# PowerSCH.net
KiCad netlist of a schematic drawn in Altium Designer
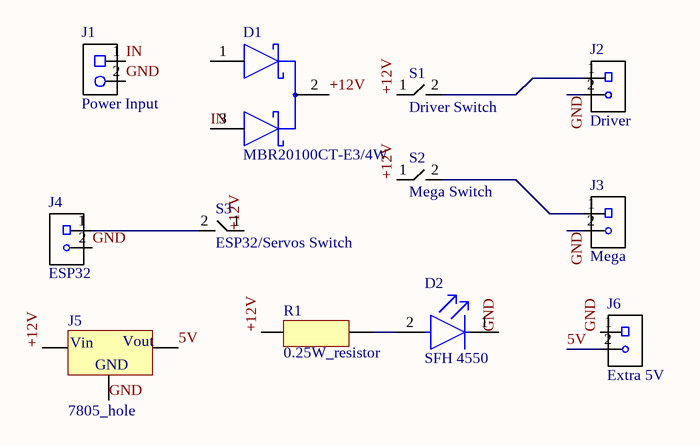
[diagram p0: PowerSCH.SchDoc]

(export (version "E")
  (design (tool "Eeschema 10.0.6"))
  (components
    (comp (ref "D1")
      (value "MBR20100CT-E3/4W")
      (footprint "FP-MBR20100CT-E3-4W-MFG")
      (description "MBR20100CT-E3/4W Dual Common-Cathode High-Voltage Schottky Rectifier")
      (libsource (lib "Altium Content Vault") (part "213139fa27cf652ab25f6c90a0a0ee5"))
    )
    (comp (ref "D2")
      (value "SFH 4550")
      (footprint "FP-SFH_4550-MFG")
      (description "Infrared Emitter, 3 , T-1 3/4 (5mm), 100 mA, 1.5 V, 12 ns, 12 ns")
      (fields (field (name "OCTOPART") "https://octopart.com/sfh+4550-osram+opto-55410894"))
      (libsource (lib "Altium Content Vault") (part "75a0115997dd6a71327e26aab64f6f8"))
    )
    (comp (ref "J1")
      (value "Power Input")
      (footprint "Barrier Terminal 2P")
      (fields
        (field (name "MANUFACTURER") "DORABO")
        (field (name "MANUFACTURER PART #") "DBT50G-9.5-2P-BK-P OGC")
        (field (name "SELLER PART #") "3496300101634")
      )
      (libsource (lib "SCH_LIB2SchLib") (part "Barrier Terminal 2P"))
    )
    (comp (ref "J2")
      (value "Driver")
      (footprint "Screw Terminal 2 pins")
      (fields (field (name "MANUFACTURER") "CUI") (field (name "MANUFACTURER PART NUMBER") "TB004-508-02BE"))
      (libsource (lib "SCH_LIB2SchLib") (part "Screw Terminal 2 pins"))
    )
    (comp (ref "J3")
      (value "Mega")
      (footprint "Screw Terminal 2 pins")
      (fields (field (name "MANUFACTURER") "CUI") (field (name "MANUFACTURER PART NUMBER") "TB004-508-02BE"))
      (libsource (lib "SCH_LIB2SchLib") (part "Screw Terminal 2 pins"))
    )
    (comp (ref "J4")
      (value "ESP32")
      (footprint "Screw Terminal 2 pins")
      (fields (field (name "MANUFACTURER") "CUI") (field (name "MANUFACTURER PART NUMBER") "TB004-508-02BE"))
      (libsource (lib "SCH_LIB2SchLib") (part "Screw Terminal 2 pins"))
    )
    (comp (ref "J5")
      (value "7805_hole")
      (footprint "780X_hole")
      (libsource (lib "Negm_3") (part "7805_hole"))
    )
    (comp (ref "J6")
      (value "Extra 5V")
      (footprint "Screw Terminal 2 pins")
      (fields (field (name "MANUFACTURER") "CUI") (field (name "MANUFACTURER PART NUMBER") "TB004-508-02BE"))
      (libsource (lib "SCH_LIB2SchLib") (part "Screw Terminal 2 pins"))
    )
    (comp (ref "R1")
      (value "0.25W_resistor")
      (footprint "0.25W_resistor")
      (libsource (lib "negm_library") (part "0.25W_resistor"))
    )
    (comp (ref "S1")
      (value "Driver Switch")
      (footprint "ON/OFF_Switch_17*11")
      (libsource (lib "Negm_3") (part "ON/OFF_Switch_17*11"))
    )
    (comp (ref "S2")
      (value "Mega Switch")
      (footprint "ON/OFF_Switch_17*11")
      (libsource (lib "Negm_3") (part "ON/OFF_Switch_17*11"))
    )
    (comp (ref "S3")
      (value "ESP32/Servos Switch")
      (footprint "ON/OFF_Switch_17*11")
      (libsource (lib "Negm_3") (part "ON/OFF_Switch_17*11"))
    )
  )
  (nets
    (net (code "1") (name "/+12V") (class "Default")
      (node (ref "D1") (pin "2") (pinfunction "COMMON_CATHODE_2") (pintype "passive"))
      (node (ref "J5") (pin "1") (pinfunction "1_1") (pintype "passive"))
      (node (ref "R1") (pin "2") (pinfunction "2_2") (pintype "passive"))
      (node (ref "S1") (pin "1") (pinfunction "1_1") (pintype "passive"))
      (node (ref "S2") (pin "1") (pinfunction "1_1") (pintype "passive"))
      (node (ref "S3") (pin "1") (pinfunction "1_1") (pintype "passive"))
    )
    (net (code "2") (name "/5V") (class "Default")
      (node (ref "J5") (pin "2") (pinfunction "2_2") (pintype "passive"))
      (node (ref "J6") (pin "2") (pintype "passive"))
    )
    (net (code "3") (name "/GND") (class "Default")
      (node (ref "D2") (pin "1") (pinfunction "C_1") (pintype "passive"))
      (node (ref "J1") (pin "2") (pinfunction "-_2") (pintype "passive"))
      (node (ref "J2") (pin "2") (pintype "passive"))
      (node (ref "J3") (pin "2") (pintype "passive"))
      (node (ref "J4") (pin "2") (pintype "passive"))
      (node (ref "J5") (pin "3") (pinfunction "3_3") (pintype "passive"))
      (node (ref "J6") (pin "1") (pinfunction "1_1") (pintype "passive"))
    )
    (net (code "4") (name "/IN") (class "Default")
      (node (ref "D1") (pin "3") (pinfunction "2_ANODE_3") (pintype "passive"))
      (node (ref "J1") (pin "1") (pinfunction "+_1") (pintype "passive"))
    )
    (net (code "5") (name "Net-(D2-A)") (class "Default")
      (node (ref "D2") (pin "2") (pinfunction "A_2") (pintype "passive"))
      (node (ref "R1") (pin "1") (pinfunction "1_1") (pintype "passive"))
    )
    (net (code "6") (name "Net-(J2-Pad1)") (class "Default")
      (node (ref "J2") (pin "1") (pinfunction "1_1") (pintype "passive"))
      (node (ref "S1") (pin "2") (pinfunction "2_2") (pintype "passive"))
    )
    (net (code "7") (name "Net-(J3-Pad1)") (class "Default")
      (node (ref "J3") (pin "1") (pinfunction "1_1") (pintype "passive"))
      (node (ref "S2") (pin "2") (pinfunction "2_2") (pintype "passive"))
    )
    (net (code "8") (name "Net-(J4-Pad1)") (class "Default")
      (node (ref "J4") (pin "1") (pinfunction "1_1") (pintype "passive"))
      (node (ref "S3") (pin "2") (pinfunction "2_2") (pintype "passive"))
    )
    (net (code "9") (name "unconnected-(D1-1_ANODE-Pad1)") (class "Default")
      (node (ref "D1") (pin "1") (pinfunction "1_ANODE_1") (pintype "passive"))
    )
  )
)
